# BU_14-AT10.net
KiCad netlist of a schematic drawn in Altium Designer
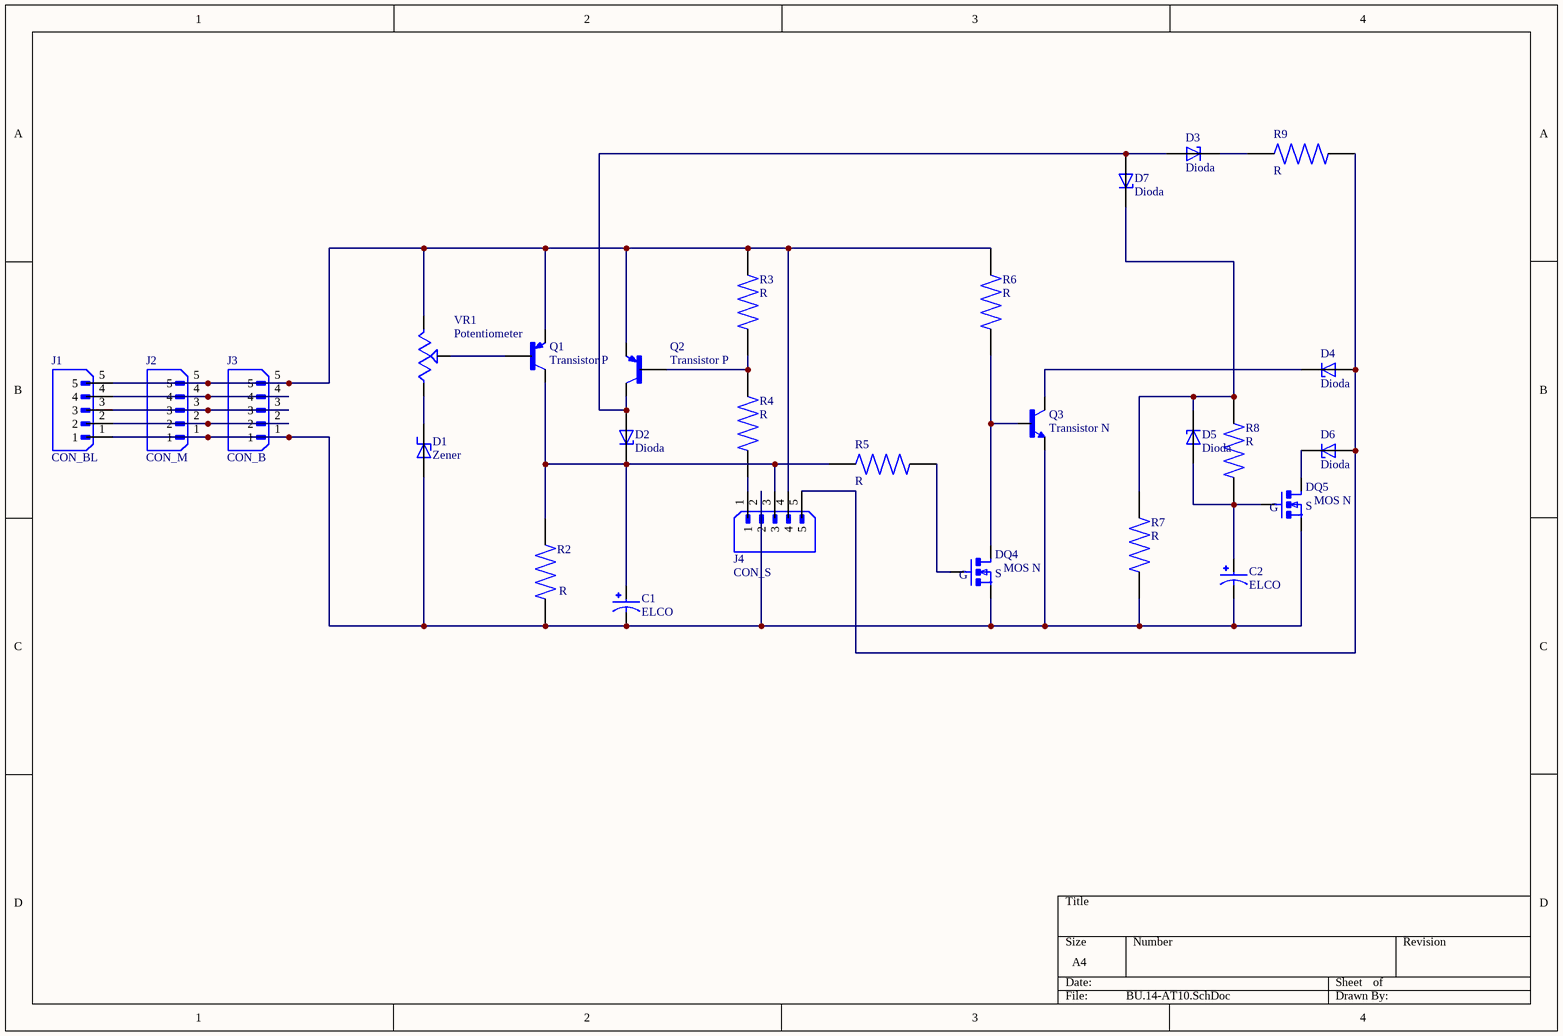
[diagram p0: BU.14-AT10.SchDoc]

(export (version "E")
  (design (tool "Eeschema 10.0.6"))
  (components
    (comp (ref "C1")
      (value "ELCO")
      (footprint "BU.14-AT10:10mmELCO")
      (description "Cap Aluminum Lytic 22uF 10V 20% (4 X 7mm) Radial 1.5mm 30mA 1000h 105C Bulk")
      (fields (field (name "MF") "Panasonic") (field (name "MP") "EEA-GA1A220"))
      (libsource (lib "BU.14-AT10") (part "ELCO"))
    )
    (comp (ref "C2")
      (value "ELCO")
      (footprint "BU.14-AT10:10mmELCO")
      (description "Cap Aluminum Lytic 22uF 10V 20% (4 X 7mm) Radial 1.5mm 30mA 1000h 105C Bulk")
      (fields (field (name "MF") "Panasonic") (field (name "MP") "EEA-GA1A220"))
      (libsource (lib "BU.14-AT10") (part "ELCO"))
    )
    (comp (ref "D1")
      (value "Zener")
      (footprint "Zener")
      (fields (field (name "MP") "P6KE36A"))
      (libsource (lib "BU.14-AT10") (part "Zener"))
    )
    (comp (ref "D2")
      (value "Dioda")
      (footprint "1N4148 - duplicate")
      (fields (field (name "MP") "P6KE36A"))
      (libsource (lib "BU.14-AT10") (part "Dioda"))
    )
    (comp (ref "D3")
      (value "Dioda")
      (footprint "1N4148 - duplicate")
      (fields (field (name "MP") "P6KE36A"))
      (libsource (lib "BU.14-AT10") (part "Dioda"))
    )
    (comp (ref "D4")
      (value "Dioda")
      (footprint "1N4148 - duplicate")
      (fields (field (name "MP") "P6KE36A"))
      (libsource (lib "BU.14-AT10") (part "Dioda"))
    )
    (comp (ref "D5")
      (value "Dioda")
      (footprint "1N4148 - duplicate")
      (fields (field (name "MP") "P6KE36A"))
      (libsource (lib "BU.14-AT10") (part "Dioda"))
    )
    (comp (ref "D6")
      (value "Dioda")
      (footprint "1N4148 - duplicate")
      (fields (field (name "MP") "P6KE36A"))
      (libsource (lib "BU.14-AT10") (part "Dioda"))
    )
    (comp (ref "D7")
      (value "Dioda")
      (footprint "1N4148 - duplicate")
      (fields (field (name "MP") "P6KE36A"))
      (libsource (lib "BU.14-AT10") (part "Dioda"))
    )
    (comp (ref "J1")
      (value "CON_BL")
      (footprint "5POS2.1mm")
      (description "Connector Header Through Hole 5 position 0.098 (2.50mm)")
      (fields (field (name "MF") "JST Sales America Inc.") (field (name "MP") "B5B-XH-A(LF)(SN)"))
      (libsource (lib "BU.14-AT10") (part "5P JST 2.1"))
    )
    (comp (ref "J2")
      (value "CON_M")
      (footprint "5POS2mm")
      (description "Connector Header Through Hole 5 position 0.098 (2.50mm)")
      (fields (field (name "MF") "JST Sales America Inc.") (field (name "MP") "B5B-XH-A(LF)(SN)"))
      (libsource (lib "BU.14-AT10") (part "5P JST 2.0"))
    )
    (comp (ref "J3")
      (value "CON_B")
      (footprint "5POS2mm")
      (description "Connector Header Through Hole 5 position 0.098 (2.50mm)")
      (fields (field (name "MF") "JST Sales America Inc.") (field (name "MP") "B5B-XH-A(LF)(SN)"))
      (libsource (lib "BU.14-AT10") (part "5P JST 2.0"))
    )
    (comp (ref "J4")
      (value "CON_S")
      (footprint "5POS2mm")
      (description "Connector Header Through Hole 5 position 0.098 (2.50mm)")
      (fields (field (name "MF") "JST Sales America Inc.") (field (name "MP") "B5B-XH-A(LF)(SN)"))
      (libsource (lib "BU.14-AT10") (part "5P JST 2.0"))
    )
    (comp (ref "Q1")
      (value "Transistor P")
      (footprint "TO-92")
      (description "Transistor PNP 2SA1015/2SA1015Y TOSHIBA miliampere=150 V=50 TO92")
      (fields (field (name "MF") "Toshiba") (field (name "MP") "2SA1015-Y"))
      (libsource (lib "") (part "Transistor P_1"))
    )
    (comp (ref "Q2")
      (value "Transistor P")
      (footprint "TO-92")
      (description "Transistor PNP 2SA1015/2SA1015Y TOSHIBA miliampere=150 V=50 TO92")
      (fields (field (name "MF") "Toshiba") (field (name "MP") "2SA1015-Y"))
      (libsource (lib "BU.14-AT10") (part "Transistor P"))
    )
    (comp (ref "Q3")
      (value "Transistor N")
      (footprint "TO-92")
      (description "TRANS NPN 40V 200MA TO92-3")
      (fields (field (name "MP") "2N3904") (field (name "MF") "Rectron"))
      (libsource (lib "BU.14-AT10") (part "Transistor N"))
    )
    (comp (ref "Q4")
      (value "MOS N")
      (footprint "TO-92")
      (description "MOSFET TO-220 N-CH 50V 30A")
      (fields (field (name "MF") "STMicroelectronics") (field (name "MP") "BUZ71"))
      (libsource (lib "BU.14-AT10") (part "MOS N"))
    )
    (comp (ref "Q5")
      (value "MOS N")
      (footprint "TO-92")
      (description "MOSFET TO-220 N-CH 50V 30A")
      (fields (field (name "MF") "STMicroelectronics") (field (name "MP") "BUZ71"))
      (libsource (lib "BU.14-AT10") (part "MOS N"))
    )
    (comp (ref "R2")
      (value "R")
      (footprint "BU.14-AT10:DIP Resistor")
      (description "1.33 kOhms Â±1% 0.25W, 1/4W Through Hole Resistor Axial Metal Film")
      (fields (field (name "MF") "Yageo") (field (name "MP") "MFR-25FBF52-1K33"))
      (libsource (lib "BU.14-AT10") (part "R"))
    )
    (comp (ref "R3")
      (value "R")
      (footprint "BU.14-AT10:DIP Resistor")
      (description "1.33 kOhms Â±1% 0.25W, 1/4W Through Hole Resistor Axial Metal Film")
      (fields (field (name "MF") "Yageo") (field (name "MP") "MFR-25FBF52-1K33"))
      (libsource (lib "BU.14-AT10") (part "R"))
    )
    (comp (ref "R4")
      (value "R")
      (footprint "BU.14-AT10:DIP Resistor")
      (description "1.33 kOhms Â±1% 0.25W, 1/4W Through Hole Resistor Axial Metal Film")
      (fields (field (name "MF") "Yageo") (field (name "MP") "MFR-25FBF52-1K33"))
      (libsource (lib "BU.14-AT10") (part "R"))
    )
    (comp (ref "R5")
      (value "R")
      (footprint "BU.14-AT10:DIP Resistor")
      (description "1.33 kOhms Â±1% 0.25W, 1/4W Through Hole Resistor Axial Metal Film")
      (fields (field (name "MF") "Yageo") (field (name "MP") "MFR-25FBF52-1K33"))
      (libsource (lib "BU.14-AT10") (part "R"))
    )
    (comp (ref "R6")
      (value "R")
      (footprint "BU.14-AT10:DIP Resistor")
      (description "1.33 kOhms Â±1% 0.25W, 1/4W Through Hole Resistor Axial Metal Film")
      (fields (field (name "MF") "Yageo") (field (name "MP") "MFR-25FBF52-1K33"))
      (libsource (lib "BU.14-AT10") (part "R"))
    )
    (comp (ref "R7")
      (value "R")
      (footprint "BU.14-AT10:DIP Resistor")
      (description "1.33 kOhms Â±1% 0.25W, 1/4W Through Hole Resistor Axial Metal Film")
      (fields (field (name "MF") "Yageo") (field (name "MP") "MFR-25FBF52-1K33"))
      (libsource (lib "BU.14-AT10") (part "R"))
    )
    (comp (ref "R8")
      (value "R")
      (footprint "BU.14-AT10:DIP Resistor")
      (description "1.33 kOhms Â±1% 0.25W, 1/4W Through Hole Resistor Axial Metal Film")
      (fields (field (name "MF") "Yageo") (field (name "MP") "MFR-25FBF52-1K33"))
      (libsource (lib "BU.14-AT10") (part "R"))
    )
    (comp (ref "R9")
      (value "R")
      (footprint "BU.14-AT10:DIP Resistor")
      (description "1.33 kOhms Â±1% 0.25W, 1/4W Through Hole Resistor Axial Metal Film")
      (fields (field (name "MF") "Yageo") (field (name "MP") "MFR-25FBF52-1K33"))
      (libsource (lib "BU.14-AT10") (part "R"))
    )
    (comp (ref "VR1")
      (value "Potentiometer")
      (footprint "Trimpot")
      (description "10 mm, Vertical, Logarithmic, 50 kÎ©, Through Hole, D-cut Rotary Potentiometer")
      (fields (field (name "MF") "Same Sky") (field (name "MP") "PT01-D225D-A503"))
      (libsource (lib "BU.14-AT10") (part "Potentiometer"))
    )
  )
  (nets
    (net (code "1") (name "Net-(D1-C)") (class "Default")
      (node (ref "D1") (pin "K") (pinfunction "C_K") (pintype "passive"))
      (node (ref "VR1") (pin "3") (pinfunction "3_3") (pintype "passive"))
    )
    (net (code "2") (name "Net-(D2-C)") (class "Default")
      (node (ref "C1") (pin "P") (pinfunction "P_P") (pintype "passive"))
      (node (ref "D2") (pin "K") (pinfunction "C_K") (pintype "passive"))
      (node (ref "J4") (pin "3") (pinfunction "3_3") (pintype "passive"))
      (node (ref "Q1") (pin "3") (pinfunction "C_3") (pintype "passive"))
      (node (ref "R2") (pin "2") (pinfunction "2_2") (pintype "passive"))
      (node (ref "R5") (pin "1") (pinfunction "1_1") (pintype "passive"))
    )
    (net (code "3") (name "Net-(D3-C)") (class "Default")
      (node (ref "D3") (pin "K") (pinfunction "C_K") (pintype "passive"))
      (node (ref "R9") (pin "1") (pinfunction "1_1") (pintype "passive"))
    )
    (net (code "4") (name "Net-(D4-C)") (class "Default")
      (node (ref "D4") (pin "K") (pinfunction "C_K") (pintype "passive"))
      (node (ref "Q3") (pin "3") (pinfunction "C_3") (pintype "passive"))
    )
    (net (code "5") (name "Net-(D4-PadA)") (class "Default")
      (node (ref "D4") (pin "A") (pinfunction "A_A") (pintype "passive"))
      (node (ref "D6") (pin "A") (pinfunction "A_A") (pintype "passive"))
      (node (ref "J4") (pin "5") (pinfunction "5_5") (pintype "passive"))
      (node (ref "R9") (pin "2") (pinfunction "2_2") (pintype "passive"))
    )
    (net (code "6") (name "Net-(D5-C)") (class "Default")
      (node (ref "D5") (pin "K") (pinfunction "C_K") (pintype "passive"))
      (node (ref "D7") (pin "K") (pinfunction "C_K") (pintype "passive"))
      (node (ref "R7") (pin "2") (pinfunction "2_2") (pintype "passive"))
      (node (ref "R8") (pin "2") (pinfunction "2_2") (pintype "passive"))
    )
    (net (code "7") (name "Net-(D6-C)") (class "Default")
      (node (ref "D6") (pin "K") (pinfunction "C_K") (pintype "passive"))
      (node (ref "Q5") (pin "3") (pinfunction "D_3") (pintype "passive"))
    )
    (net (code "8") (name "Net-(J1-Pad2)") (class "Default")
      (node (ref "J1") (pin "2") (pinfunction "2_2") (pintype "passive"))
      (node (ref "J2") (pin "2") (pinfunction "2_2") (pintype "passive"))
      (node (ref "J3") (pin "2") (pinfunction "2_2") (pintype "passive"))
    )
    (net (code "9") (name "Net-(J1-Pad3)") (class "Default")
      (node (ref "J1") (pin "3") (pinfunction "3_3") (pintype "passive"))
      (node (ref "J2") (pin "3") (pinfunction "3_3") (pintype "passive"))
      (node (ref "J3") (pin "3") (pinfunction "3_3") (pintype "passive"))
    )
    (net (code "10") (name "Net-(J1-Pad4)") (class "Default")
      (node (ref "J1") (pin "4") (pinfunction "4_4") (pintype "passive"))
      (node (ref "J2") (pin "4") (pinfunction "4_4") (pintype "passive"))
      (node (ref "J3") (pin "4") (pinfunction "4_4") (pintype "passive"))
    )
    (net (code "11") (name "Net-(J4-Pad1)") (class "Default")
      (node (ref "J4") (pin "1") (pinfunction "1_1") (pintype "passive"))
      (node (ref "R4") (pin "1") (pinfunction "1_1") (pintype "passive"))
    )
    (net (code "12") (name "Net-(Q1-B)") (class "Default")
      (node (ref "Q1") (pin "2") (pinfunction "B_2") (pintype "passive"))
      (node (ref "VR1") (pin "2") (pinfunction "2_2") (pintype "passive"))
    )
    (net (code "13") (name "Net-(Q1-E)") (class "Default")
      (node (ref "J1") (pin "5") (pinfunction "5_5") (pintype "passive"))
      (node (ref "J2") (pin "5") (pinfunction "5_5") (pintype "passive"))
      (node (ref "J3") (pin "5") (pinfunction "5_5") (pintype "passive"))
      (node (ref "J4") (pin "4") (pinfunction "4_4") (pintype "passive"))
      (node (ref "Q1") (pin "1") (pinfunction "E_1") (pintype "passive"))
      (node (ref "Q2") (pin "1") (pinfunction "E_1") (pintype "passive"))
      (node (ref "R3") (pin "2") (pinfunction "2_2") (pintype "passive"))
      (node (ref "R6") (pin "2") (pinfunction "2_2") (pintype "passive"))
      (node (ref "VR1") (pin "1") (pinfunction "1_1") (pintype "passive"))
    )
    (net (code "14") (name "Net-(Q2-B)") (class "Default")
      (node (ref "Q2") (pin "2") (pinfunction "B_2") (pintype "passive"))
      (node (ref "R3") (pin "1") (pinfunction "1_1") (pintype "passive"))
      (node (ref "R4") (pin "2") (pinfunction "2_2") (pintype "passive"))
    )
    (net (code "15") (name "Net-(Q2-C)") (class "Default")
      (node (ref "D2") (pin "A") (pinfunction "A_A") (pintype "passive"))
      (node (ref "D3") (pin "A") (pinfunction "A_A") (pintype "passive"))
      (node (ref "D7") (pin "A") (pinfunction "A_A") (pintype "passive"))
      (node (ref "Q2") (pin "3") (pinfunction "C_3") (pintype "passive"))
    )
    (net (code "16") (name "Net-(Q3-B)") (class "Default")
      (node (ref "Q3") (pin "2") (pinfunction "B_2") (pintype "passive"))
      (node (ref "Q4") (pin "3") (pinfunction "D_3") (pintype "passive"))
      (node (ref "R6") (pin "1") (pinfunction "1_1") (pintype "passive"))
    )
    (net (code "17") (name "Net-(Q3-E)") (class "Default")
      (node (ref "C1") (pin "N") (pinfunction "N_N") (pintype "passive"))
      (node (ref "C2") (pin "N") (pinfunction "N_N") (pintype "passive"))
      (node (ref "D1") (pin "A") (pinfunction "A_A") (pintype "passive"))
      (node (ref "J1") (pin "1") (pinfunction "1_1") (pintype "passive"))
      (node (ref "J2") (pin "1") (pinfunction "1_1") (pintype "passive"))
      (node (ref "J3") (pin "1") (pinfunction "1_1") (pintype "passive"))
      (node (ref "J4") (pin "2") (pinfunction "2_2") (pintype "passive"))
      (node (ref "Q3") (pin "1") (pinfunction "E_1") (pintype "passive"))
      (node (ref "Q4") (pin "1") (pinfunction "S_1") (pintype "passive"))
      (node (ref "Q5") (pin "1") (pinfunction "S_1") (pintype "passive"))
      (node (ref "R2") (pin "1") (pinfunction "1_1") (pintype "passive"))
      (node (ref "R7") (pin "1") (pinfunction "1_1") (pintype "passive"))
    )
    (net (code "18") (name "Net-(Q4-G)") (class "Default")
      (node (ref "Q4") (pin "2") (pinfunction "G_2") (pintype "passive"))
      (node (ref "R5") (pin "2") (pinfunction "2_2") (pintype "passive"))
    )
    (net (code "19") (name "Net-(Q5-G)") (class "Default")
      (node (ref "C2") (pin "P") (pinfunction "P_P") (pintype "passive"))
      (node (ref "D5") (pin "A") (pinfunction "A_A") (pintype "passive"))
      (node (ref "Q5") (pin "2") (pinfunction "G_2") (pintype "passive"))
      (node (ref "R8") (pin "1") (pinfunction "1_1") (pintype "passive"))
    )
  )
)
